# power.net
KiCad netlist of a schematic drawn in Altium Designer
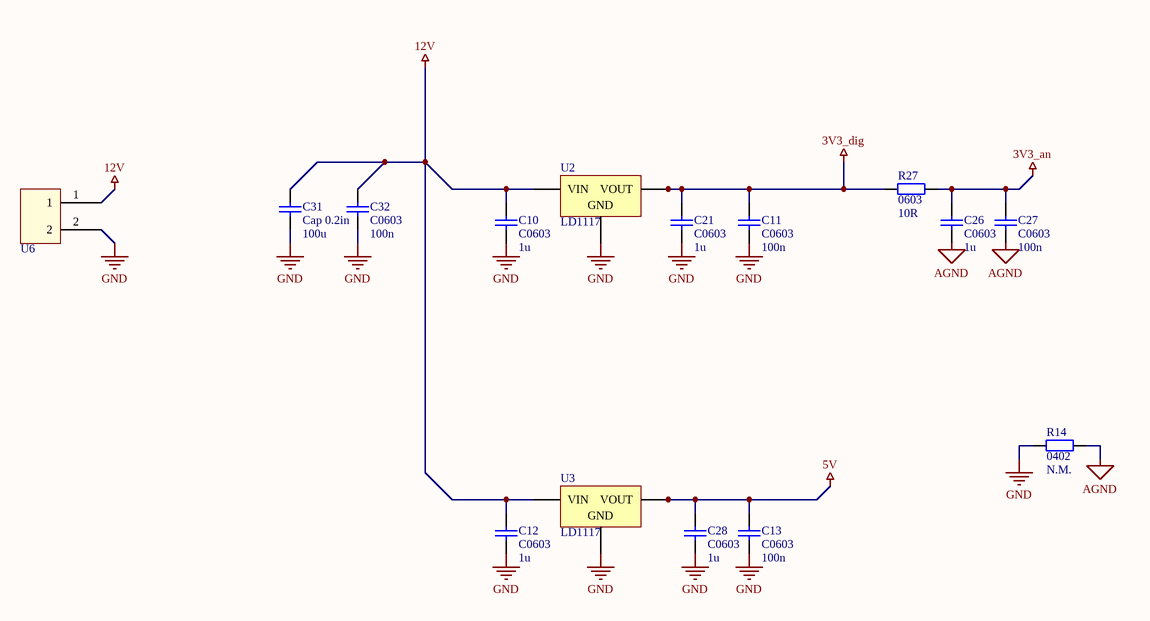
[diagram p0: power.SchDoc]

(export (version "E")
  (design (tool "Eeschema 10.0.6"))
  (components
    (comp (ref "C10")
      (value "1u")
      (footprint "C0603")
      (description "Generic capacitor")
      (libsource (lib "_RLC") (part "Cap"))
    )
    (comp (ref "C11")
      (value "100n")
      (footprint "C0603")
      (description "Generic capacitor")
      (libsource (lib "_RLC") (part "Cap"))
    )
    (comp (ref "C12")
      (value "1u")
      (footprint "C0603")
      (description "Generic capacitor")
      (libsource (lib "_RLC") (part "Cap"))
    )
    (comp (ref "C13")
      (value "100n")
      (footprint "C0603")
      (description "Generic capacitor")
      (libsource (lib "_RLC") (part "Cap"))
    )
    (comp (ref "C21")
      (value "1u")
      (footprint "C0603")
      (description "Generic capacitor")
      (libsource (lib "_RLC") (part "Cap"))
    )
    (comp (ref "C26")
      (value "1u")
      (footprint "C0603")
      (description "Generic capacitor")
      (libsource (lib "_RLC") (part "Cap"))
    )
    (comp (ref "C27")
      (value "100n")
      (footprint "C0603")
      (description "Generic capacitor")
      (libsource (lib "_RLC") (part "Cap"))
    )
    (comp (ref "C28")
      (value "1u")
      (footprint "C0603")
      (description "Generic capacitor")
      (libsource (lib "_RLC") (part "Cap"))
    )
    (comp (ref "C31")
      (value "100u")
      (footprint "Cap 0.2in")
      (description "Generic capacitor")
      (libsource (lib "_RLC") (part "Cap"))
    )
    (comp (ref "C32")
      (value "100n")
      (footprint "C0603")
      (description "Generic capacitor")
      (libsource (lib "_RLC") (part "Cap"))
    )
    (comp (ref "R14")
      (value "N.M.")
      (footprint "0402")
      (description "Generic resistor")
      (libsource (lib "_RLC") (part "Res"))
    )
    (comp (ref "R27")
      (value "10R")
      (footprint "0603")
      (description "Generic resistor")
      (libsource (lib "_RLC") (part "Res"))
    )
    (comp (ref "U2")
      (value "LD1117")
      (footprint "TO-252")
      (description "Low drop positive voltage regulator")
      (libsource (lib "_Microcircuits") (part "LD1117"))
    )
    (comp (ref "U3")
      (value "LD1117")
      (footprint "TO-252")
      (description "Low drop positive voltage regulator")
      (libsource (lib "_Microcircuits") (part "LD1117"))
    )
    (comp (ref "U6")
      (value "ARK Terminal Block; 2-pin")
      (footprint "ARK2")
      (libsource (lib "_Connectors") (part "ARK Terminal Block; 2-pin"))
    )
  )
  (nets
    (net (code "1") (name "3V3_an") (class "Default")
      (node (ref "C26") (pin "1") (pinfunction "1_1") (pintype "passive"))
      (node (ref "C27") (pin "1") (pinfunction "1_1") (pintype "passive"))
      (node (ref "R27") (pin "2") (pinfunction "2_2") (pintype "passive"))
    )
    (net (code "2") (name "3V3_dig") (class "Default")
      (node (ref "C11") (pin "1") (pinfunction "1_1") (pintype "passive"))
      (node (ref "C21") (pin "1") (pinfunction "1_1") (pintype "passive"))
      (node (ref "R27") (pin "1") (pinfunction "1_1") (pintype "passive"))
      (node (ref "U2") (pin "2") (pinfunction "VOUT_2") (pintype "power_in"))
      (node (ref "U2") (pin "4") (pinfunction "VOUT_4") (pintype "power_in"))
      (node (ref "U2") (pin "5") (pinfunction "VOUT_5") (pintype "power_in"))
      (node (ref "U2") (pin "6") (pinfunction "VOUT_6") (pintype "power_in"))
    )
    (net (code "3") (name "5V") (class "Default")
      (node (ref "C13") (pin "1") (pinfunction "1_1") (pintype "passive"))
      (node (ref "C28") (pin "1") (pinfunction "1_1") (pintype "passive"))
      (node (ref "U3") (pin "2") (pinfunction "VOUT_2") (pintype "power_in"))
      (node (ref "U3") (pin "4") (pinfunction "VOUT_4") (pintype "power_in"))
      (node (ref "U3") (pin "5") (pinfunction "VOUT_5") (pintype "power_in"))
      (node (ref "U3") (pin "6") (pinfunction "VOUT_6") (pintype "power_in"))
    )
    (net (code "4") (name "12V") (class "Default")
      (node (ref "C10") (pin "1") (pinfunction "1_1") (pintype "passive"))
      (node (ref "C12") (pin "1") (pinfunction "1_1") (pintype "passive"))
      (node (ref "C31") (pin "1") (pinfunction "1_1") (pintype "passive"))
      (node (ref "C32") (pin "1") (pinfunction "1_1") (pintype "passive"))
      (node (ref "U2") (pin "3") (pinfunction "VIN_3") (pintype "power_in"))
      (node (ref "U3") (pin "3") (pinfunction "VIN_3") (pintype "power_in"))
      (node (ref "U6") (pin "1") (pinfunction "1_1") (pintype "passive"))
    )
    (net (code "5") (name "AGND") (class "Default")
      (node (ref "C26") (pin "2") (pinfunction "2_2") (pintype "passive"))
      (node (ref "C27") (pin "2") (pinfunction "2_2") (pintype "passive"))
      (node (ref "R14") (pin "2") (pinfunction "2_2") (pintype "passive"))
    )
    (net (code "6") (name "GND") (class "Default")
      (node (ref "C10") (pin "2") (pinfunction "2_2") (pintype "passive"))
      (node (ref "C11") (pin "2") (pinfunction "2_2") (pintype "passive"))
      (node (ref "C12") (pin "2") (pinfunction "2_2") (pintype "passive"))
      (node (ref "C13") (pin "2") (pinfunction "2_2") (pintype "passive"))
      (node (ref "C21") (pin "2") (pinfunction "2_2") (pintype "passive"))
      (node (ref "C28") (pin "2") (pinfunction "2_2") (pintype "passive"))
      (node (ref "C31") (pin "2") (pinfunction "2_2") (pintype "passive"))
      (node (ref "C32") (pin "2") (pinfunction "2_2") (pintype "passive"))
      (node (ref "R14") (pin "1") (pinfunction "1_1") (pintype "passive"))
      (node (ref "U2") (pin "1") (pinfunction "GND_1") (pintype "power_in"))
      (node (ref "U3") (pin "1") (pinfunction "GND_1") (pintype "power_in"))
      (node (ref "U6") (pin "2") (pinfunction "2_2") (pintype "passive"))
    )
  )
)
